# OSSI-1_Interface_Board.net
KiCad netlist of a schematic drawn in EAGLE
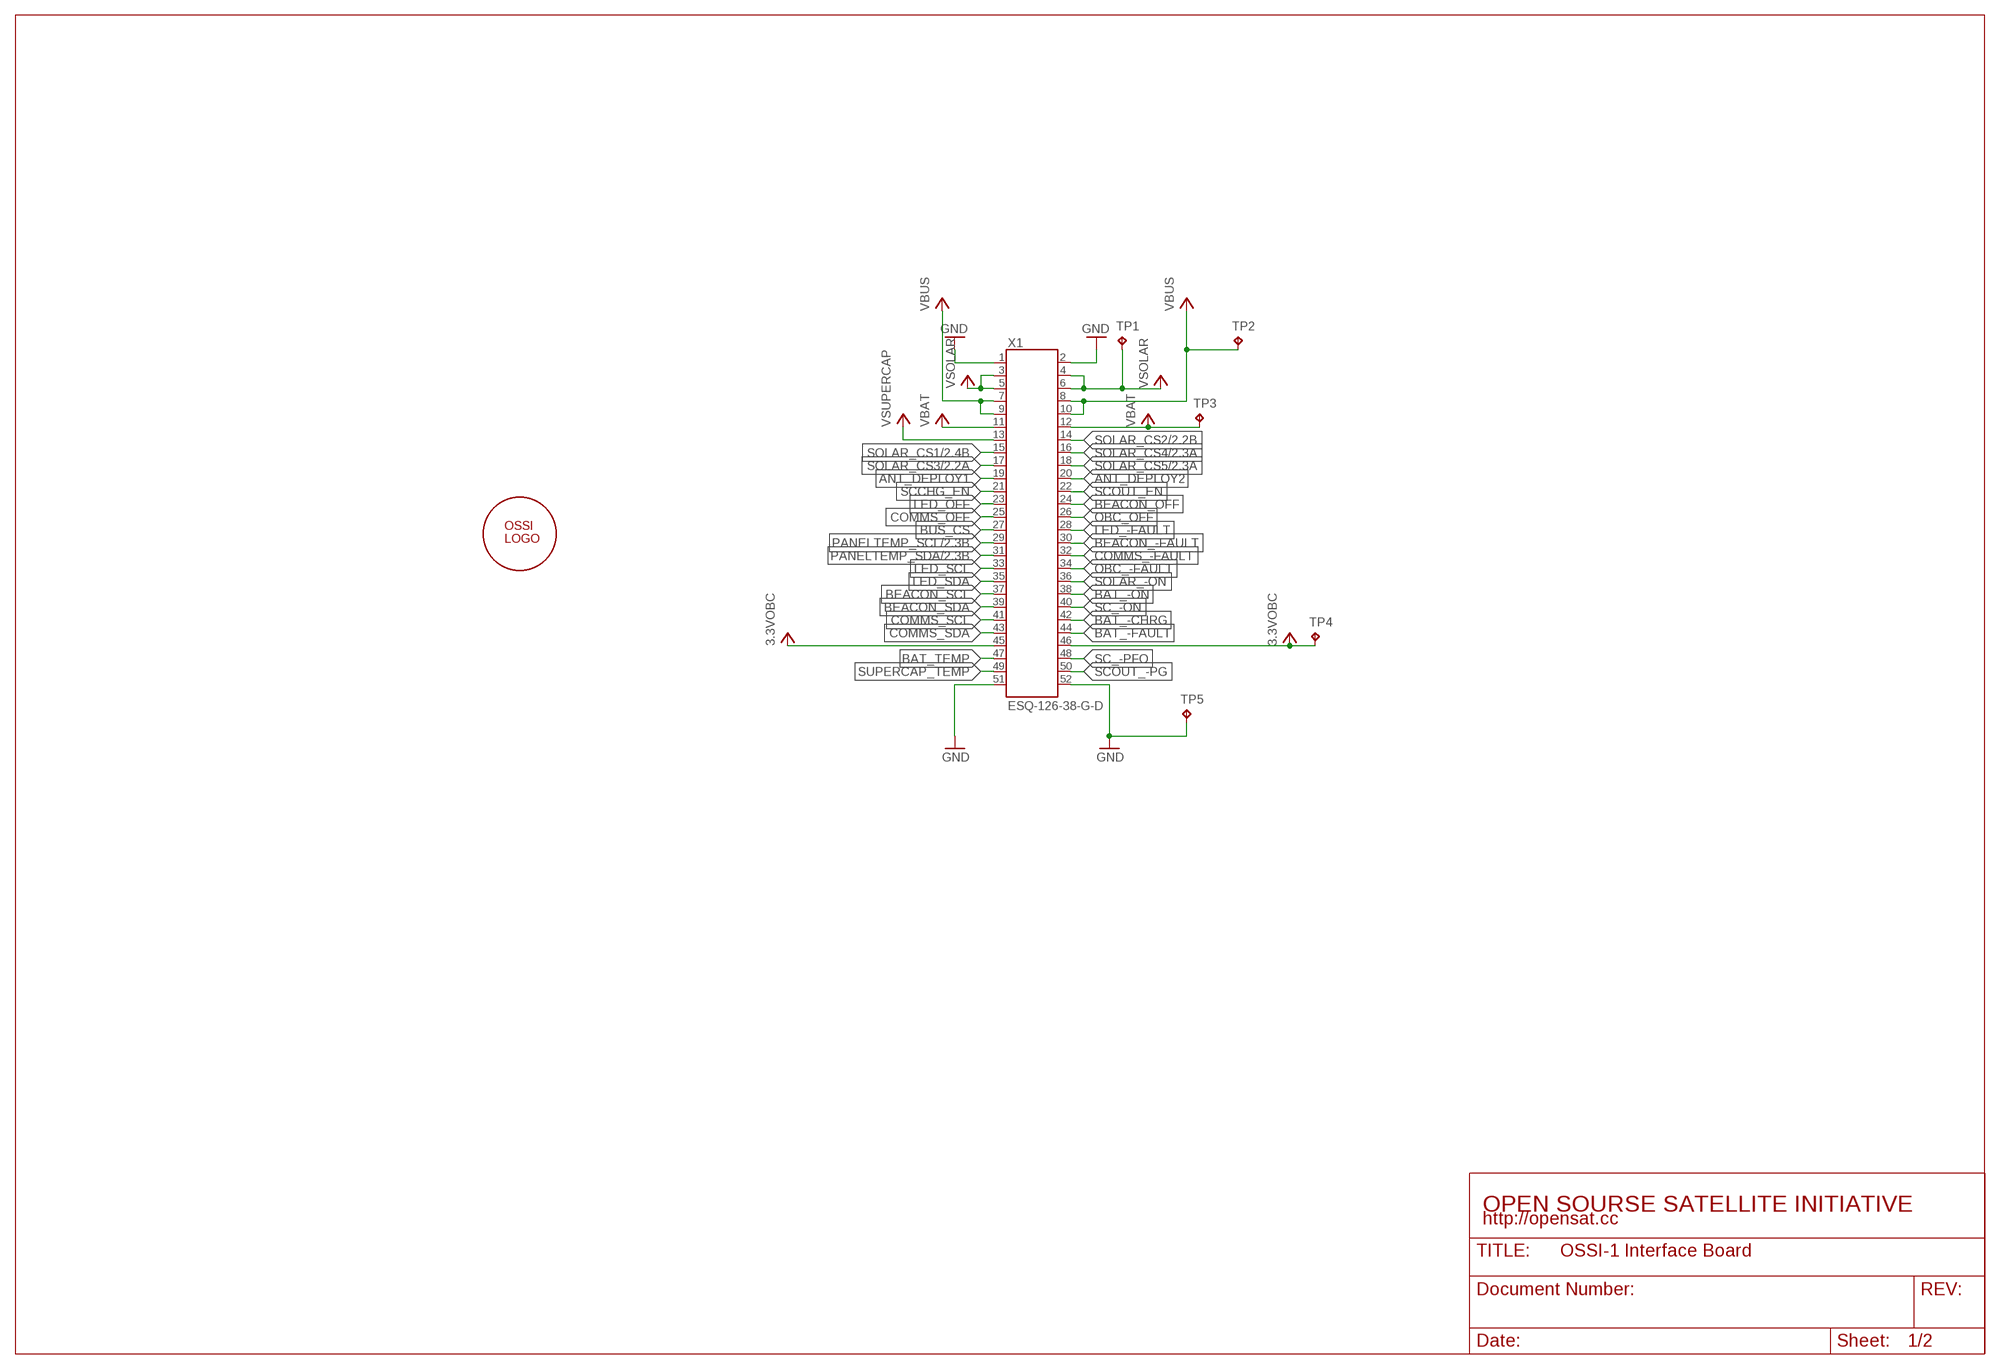
[diagram p0: schematic, sheet 1]
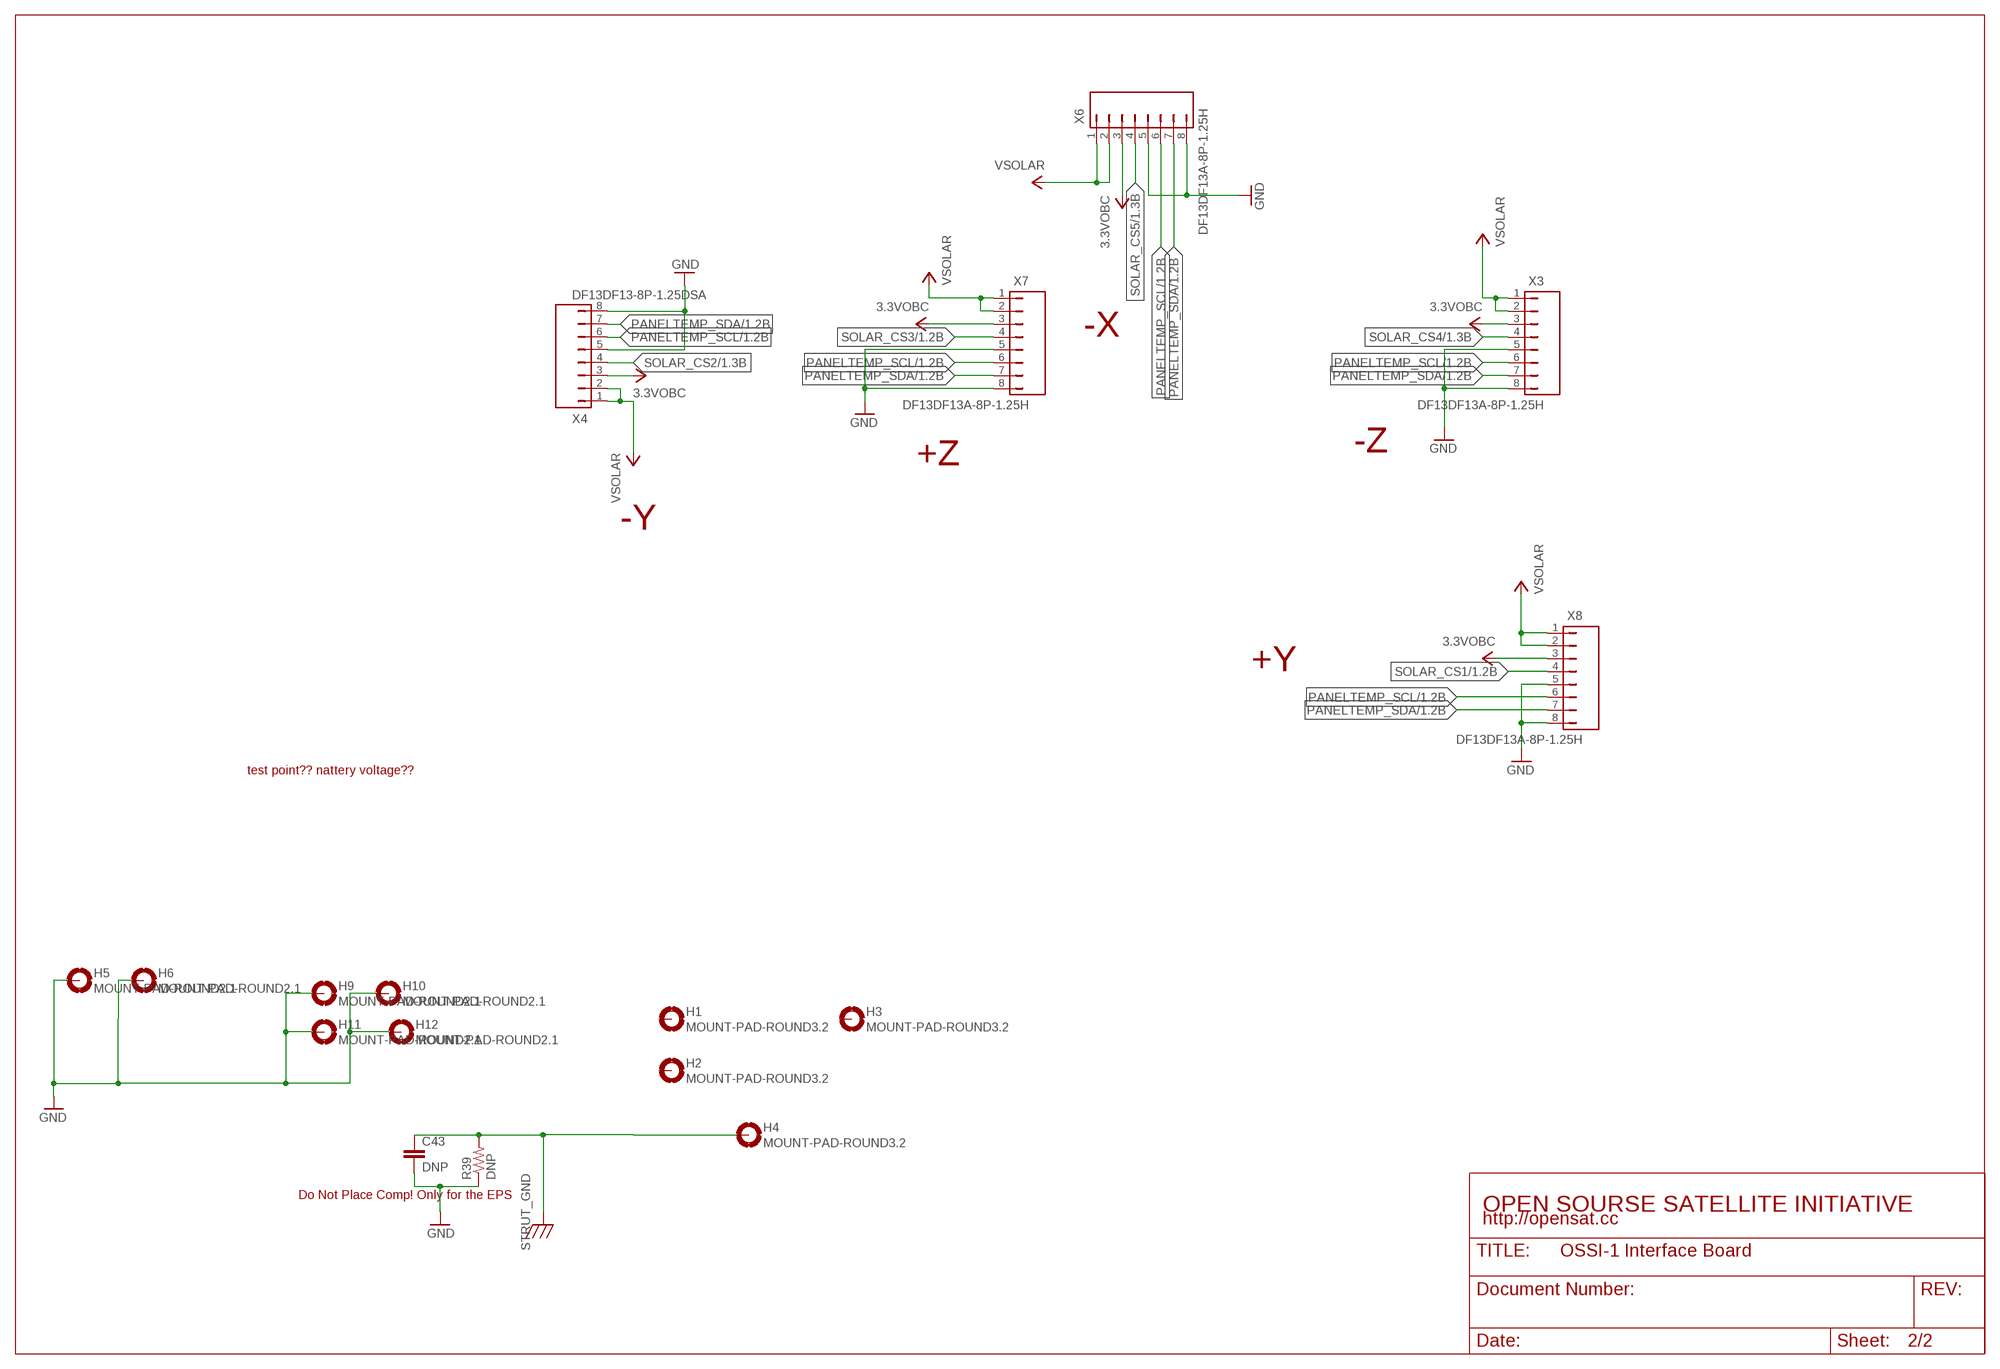
[diagram p1: schematic, sheet 2]

(export (version "E")
  (design (tool "Eeschema 10.0.6"))
  (components
    (comp (ref "TP1")
      (value "TP")
      (footprint "eagle-import:TP-13")
      (libsource (lib "eagle-import") (part "TP"))
    )
    (comp (ref "TP2")
      (value "TP")
      (footprint "eagle-import:TP-13")
      (libsource (lib "eagle-import") (part "TP"))
    )
    (comp (ref "TP3")
      (value "TP")
      (footprint "eagle-import:TP-13")
      (libsource (lib "eagle-import") (part "TP"))
    )
    (comp (ref "TP4")
      (value "TP")
      (footprint "eagle-import:TP-13")
      (libsource (lib "eagle-import") (part "TP"))
    )
    (comp (ref "TP5")
      (value "TP")
      (footprint "eagle-import:TP-13")
      (libsource (lib "eagle-import") (part "TP"))
    )
    (comp (ref "U$1")
      (value "OSSILOGO-10")
      (footprint "eagle-import:OSSILOGO1010")
      (libsource (lib "eagle-import") (part "OSSILOGO-10"))
    )
    (comp (ref "X1")
      (value "ESQ-126-38-G-D")
      (footprint "eagle-import:ESQ-126-XX-X-D")
      (libsource (lib "eagle-import") (part "ESQ-126-38-G-D"))
    )
    (comp (ref "C43")
      (value "DNP")
      (footprint "eagle-import:C0805(2012)")
      (libsource (lib "eagle-import") (part "C0805(2012)"))
    )
    (comp (ref "H1")
      (value "MOUNT-PAD-ROUND3.2")
      (footprint "eagle-import:3.2-PAD-ROUND")
      (libsource (lib "eagle-import") (part "MOUNT-PAD-ROUND3.2"))
    )
    (comp (ref "H2")
      (value "MOUNT-PAD-ROUND3.2")
      (footprint "eagle-import:3.2-PAD-ROUND")
      (libsource (lib "eagle-import") (part "MOUNT-PAD-ROUND3.2"))
    )
    (comp (ref "H3")
      (value "MOUNT-PAD-ROUND3.2")
      (footprint "eagle-import:3.2-PAD-ROUND")
      (libsource (lib "eagle-import") (part "MOUNT-PAD-ROUND3.2"))
    )
    (comp (ref "H4")
      (value "MOUNT-PAD-ROUND3.2")
      (footprint "eagle-import:3.2-PAD-ROUND")
      (libsource (lib "eagle-import") (part "MOUNT-PAD-ROUND3.2"))
    )
    (comp (ref "H5")
      (value "MOUNT-PAD-ROUND2.1")
      (footprint "eagle-import:2.1-PAD-ROUND")
      (libsource (lib "eagle-import") (part "MOUNT-PAD-ROUND2.1"))
    )
    (comp (ref "H6")
      (value "MOUNT-PAD-ROUND2.1")
      (footprint "eagle-import:2.1-PAD-ROUND")
      (libsource (lib "eagle-import") (part "MOUNT-PAD-ROUND2.1"))
    )
    (comp (ref "H9")
      (value "MOUNT-PAD-ROUND2.1")
      (footprint "eagle-import:2.1-PAD-ROUND")
      (libsource (lib "eagle-import") (part "MOUNT-PAD-ROUND2.1"))
    )
    (comp (ref "H10")
      (value "MOUNT-PAD-ROUND2.1")
      (footprint "eagle-import:2.1-PAD-ROUND")
      (libsource (lib "eagle-import") (part "MOUNT-PAD-ROUND2.1"))
    )
    (comp (ref "H11")
      (value "MOUNT-PAD-ROUND2.1")
      (footprint "eagle-import:2.1-PAD-ROUND")
      (libsource (lib "eagle-import") (part "MOUNT-PAD-ROUND2.1"))
    )
    (comp (ref "H12")
      (value "MOUNT-PAD-ROUND2.1")
      (footprint "eagle-import:2.1-PAD-ROUND")
      (libsource (lib "eagle-import") (part "MOUNT-PAD-ROUND2.1"))
    )
    (comp (ref "R39")
      (value "DNP")
      (footprint "eagle-import:WSL1206")
      (libsource (lib "eagle-import") (part "RWSL1206"))
    )
    (comp (ref "X3")
      (value "DF13DF13A-8P-1.25H")
      (footprint "eagle-import:DF13A-8P")
      (libsource (lib "eagle-import") (part "DF13DF13A-8P-1.25H"))
    )
    (comp (ref "X4")
      (value "DF13DF13-8P-1.25DSA")
      (footprint "eagle-import:DF13-8P-1.25DSA")
      (libsource (lib "eagle-import") (part "DF13DF13-8P-1.25DSA"))
    )
    (comp (ref "X6")
      (value "DF13DF13A-8P-1.25H")
      (footprint "eagle-import:DF13A-8P")
      (libsource (lib "eagle-import") (part "DF13DF13A-8P-1.25H"))
    )
    (comp (ref "X7")
      (value "DF13DF13A-8P-1.25H")
      (footprint "eagle-import:DF13A-8P")
      (libsource (lib "eagle-import") (part "DF13DF13A-8P-1.25H"))
    )
    (comp (ref "X8")
      (value "DF13DF13A-8P-1.25H")
      (footprint "eagle-import:DF13A-8P")
      (libsource (lib "eagle-import") (part "DF13DF13A-8P-1.25H"))
    )
  )
  (nets
    (net (code "1") (name "3.3VOBC") (class "Default")
      (node (ref "TP4") (pin "TP") (pinfunction "TP_TP") (pintype "input"))
      (node (ref "X1") (pin "45") (pinfunction "45_45") (pintype "bidirectional"))
      (node (ref "X1") (pin "46") (pinfunction "46_46") (pintype "bidirectional"))
      (node (ref "X3") (pin "3") (pinfunction "3_3") (pintype "passive"))
      (node (ref "X4") (pin "3") (pinfunction "3_3") (pintype "passive"))
      (node (ref "X6") (pin "3") (pinfunction "3_3") (pintype "passive"))
      (node (ref "X7") (pin "3") (pinfunction "3_3") (pintype "passive"))
      (node (ref "X8") (pin "3") (pinfunction "3_3") (pintype "passive"))
    )
    (net (code "2") (name "ANT_DEPLOY1") (class "Default")
      (node (ref "X1") (pin "19") (pinfunction "19_19") (pintype "bidirectional"))
    )
    (net (code "3") (name "ANT_DEPLOY2") (class "Default")
      (node (ref "X1") (pin "20") (pinfunction "20_20") (pintype "bidirectional"))
    )
    (net (code "4") (name "BAT_-CHRG") (class "Default")
      (node (ref "X1") (pin "42") (pinfunction "42_42") (pintype "bidirectional"))
    )
    (net (code "5") (name "BAT_-FAULT") (class "Default")
      (node (ref "X1") (pin "44") (pinfunction "44_44") (pintype "bidirectional"))
    )
    (net (code "6") (name "BAT_-ON") (class "Default")
      (node (ref "X1") (pin "38") (pinfunction "38_38") (pintype "bidirectional"))
    )
    (net (code "7") (name "BAT_TEMP") (class "Default")
      (node (ref "X1") (pin "47") (pinfunction "47_47") (pintype "bidirectional"))
    )
    (net (code "8") (name "BEACON_-FAULT") (class "Default")
      (node (ref "X1") (pin "30") (pinfunction "30_30") (pintype "bidirectional"))
    )
    (net (code "9") (name "BEACON_OFF") (class "Default")
      (node (ref "X1") (pin "24") (pinfunction "24_24") (pintype "bidirectional"))
    )
    (net (code "10") (name "BEACON_SCL") (class "Default")
      (node (ref "X1") (pin "37") (pinfunction "37_37") (pintype "bidirectional"))
    )
    (net (code "11") (name "BEACON_SDA") (class "Default")
      (node (ref "X1") (pin "39") (pinfunction "39_39") (pintype "bidirectional"))
    )
    (net (code "12") (name "BUS_CS") (class "Default")
      (node (ref "X1") (pin "27") (pinfunction "27_27") (pintype "bidirectional"))
    )
    (net (code "13") (name "COMMS_-FAULT") (class "Default")
      (node (ref "X1") (pin "32") (pinfunction "32_32") (pintype "bidirectional"))
    )
    (net (code "14") (name "COMMS_OFF") (class "Default")
      (node (ref "X1") (pin "25") (pinfunction "25_25") (pintype "bidirectional"))
    )
    (net (code "15") (name "COMMS_SCL") (class "Default")
      (node (ref "X1") (pin "41") (pinfunction "41_41") (pintype "bidirectional"))
    )
    (net (code "16") (name "COMMS_SDA") (class "Default")
      (node (ref "X1") (pin "43") (pinfunction "43_43") (pintype "bidirectional"))
    )
    (net (code "17") (name "GND") (class "Default")
      (node (ref "C43") (pin "2") (pinfunction "2_2") (pintype "passive"))
      (node (ref "H10") (pin "B3,2") (pinfunction "MOUNT_B3,2") (pintype "passive"))
      (node (ref "H11") (pin "B3,2") (pinfunction "MOUNT_B3,2") (pintype "passive"))
      (node (ref "H12") (pin "B3,2") (pinfunction "MOUNT_B3,2") (pintype "passive"))
      (node (ref "H5") (pin "B3,2") (pinfunction "MOUNT_B3,2") (pintype "passive"))
      (node (ref "H6") (pin "B3,2") (pinfunction "MOUNT_B3,2") (pintype "passive"))
      (node (ref "H9") (pin "B3,2") (pinfunction "MOUNT_B3,2") (pintype "passive"))
      (node (ref "R39") (pin "P$1") (pinfunction "1_P$1") (pintype "passive"))
      (node (ref "TP5") (pin "TP") (pinfunction "TP_TP") (pintype "input"))
      (node (ref "X1") (pin "1") (pinfunction "1_1") (pintype "bidirectional"))
      (node (ref "X1") (pin "2") (pinfunction "2_2") (pintype "bidirectional"))
      (node (ref "X1") (pin "51") (pinfunction "51_51") (pintype "bidirectional"))
      (node (ref "X1") (pin "52") (pinfunction "52_52") (pintype "bidirectional"))
      (node (ref "X3") (pin "5") (pinfunction "5_5") (pintype "passive"))
      (node (ref "X3") (pin "8") (pinfunction "8_8") (pintype "passive"))
      (node (ref "X4") (pin "5") (pinfunction "5_5") (pintype "passive"))
      (node (ref "X4") (pin "8") (pinfunction "8_8") (pintype "passive"))
      (node (ref "X6") (pin "5") (pinfunction "5_5") (pintype "passive"))
      (node (ref "X6") (pin "8") (pinfunction "8_8") (pintype "passive"))
      (node (ref "X7") (pin "5") (pinfunction "5_5") (pintype "passive"))
      (node (ref "X7") (pin "8") (pinfunction "8_8") (pintype "passive"))
      (node (ref "X8") (pin "5") (pinfunction "5_5") (pintype "passive"))
      (node (ref "X8") (pin "8") (pinfunction "8_8") (pintype "passive"))
    )
    (net (code "18") (name "LED_-FAULT") (class "Default")
      (node (ref "X1") (pin "28") (pinfunction "28_28") (pintype "bidirectional"))
    )
    (net (code "19") (name "LED_OFF") (class "Default")
      (node (ref "X1") (pin "23") (pinfunction "23_23") (pintype "bidirectional"))
    )
    (net (code "20") (name "LED_SCL") (class "Default")
      (node (ref "X1") (pin "33") (pinfunction "33_33") (pintype "bidirectional"))
    )
    (net (code "21") (name "LED_SDA") (class "Default")
      (node (ref "X1") (pin "35") (pinfunction "35_35") (pintype "bidirectional"))
    )
    (net (code "22") (name "OBC_-FAULT") (class "Default")
      (node (ref "X1") (pin "34") (pinfunction "34_34") (pintype "bidirectional"))
    )
    (net (code "23") (name "OBC_OFF") (class "Default")
      (node (ref "X1") (pin "26") (pinfunction "26_26") (pintype "bidirectional"))
    )
    (net (code "24") (name "PANELTEMP_SCL") (class "Default")
      (node (ref "X1") (pin "29") (pinfunction "29_29") (pintype "bidirectional"))
      (node (ref "X3") (pin "6") (pinfunction "6_6") (pintype "passive"))
      (node (ref "X4") (pin "6") (pinfunction "6_6") (pintype "passive"))
      (node (ref "X6") (pin "6") (pinfunction "6_6") (pintype "passive"))
      (node (ref "X7") (pin "6") (pinfunction "6_6") (pintype "passive"))
      (node (ref "X8") (pin "6") (pinfunction "6_6") (pintype "passive"))
    )
    (net (code "25") (name "PANELTEMP_SDA") (class "Default")
      (node (ref "X1") (pin "31") (pinfunction "31_31") (pintype "bidirectional"))
      (node (ref "X3") (pin "7") (pinfunction "7_7") (pintype "passive"))
      (node (ref "X4") (pin "7") (pinfunction "7_7") (pintype "passive"))
      (node (ref "X6") (pin "7") (pinfunction "7_7") (pintype "passive"))
      (node (ref "X7") (pin "7") (pinfunction "7_7") (pintype "passive"))
      (node (ref "X8") (pin "7") (pinfunction "7_7") (pintype "passive"))
    )
    (net (code "26") (name "SCCHG_EN") (class "Default")
      (node (ref "X1") (pin "21") (pinfunction "21_21") (pintype "bidirectional"))
    )
    (net (code "27") (name "SCOUT_-PG") (class "Default")
      (node (ref "X1") (pin "50") (pinfunction "50_50") (pintype "bidirectional"))
    )
    (net (code "28") (name "SCOUT_EN") (class "Default")
      (node (ref "X1") (pin "22") (pinfunction "22_22") (pintype "bidirectional"))
    )
    (net (code "29") (name "SC_-ON") (class "Default")
      (node (ref "X1") (pin "40") (pinfunction "40_40") (pintype "bidirectional"))
    )
    (net (code "30") (name "SC_-PFO") (class "Default")
      (node (ref "X1") (pin "48") (pinfunction "48_48") (pintype "bidirectional"))
    )
    (net (code "31") (name "SOLAR_-ON") (class "Default")
      (node (ref "X1") (pin "36") (pinfunction "36_36") (pintype "bidirectional"))
    )
    (net (code "32") (name "SOLAR_CS1") (class "Default")
      (node (ref "X1") (pin "15") (pinfunction "15_15") (pintype "bidirectional"))
      (node (ref "X8") (pin "4") (pinfunction "4_4") (pintype "passive"))
    )
    (net (code "33") (name "SOLAR_CS2") (class "Default")
      (node (ref "X1") (pin "14") (pinfunction "14_14") (pintype "bidirectional"))
      (node (ref "X4") (pin "4") (pinfunction "4_4") (pintype "passive"))
    )
    (net (code "34") (name "SOLAR_CS3") (class "Default")
      (node (ref "X1") (pin "17") (pinfunction "17_17") (pintype "bidirectional"))
      (node (ref "X7") (pin "4") (pinfunction "4_4") (pintype "passive"))
    )
    (net (code "35") (name "SOLAR_CS4") (class "Default")
      (node (ref "X1") (pin "16") (pinfunction "16_16") (pintype "bidirectional"))
      (node (ref "X3") (pin "4") (pinfunction "4_4") (pintype "passive"))
    )
    (net (code "36") (name "SOLAR_CS5") (class "Default")
      (node (ref "X1") (pin "18") (pinfunction "18_18") (pintype "bidirectional"))
      (node (ref "X6") (pin "4") (pinfunction "4_4") (pintype "passive"))
    )
    (net (code "37") (name "STRUT_GND") (class "Default")
      (node (ref "C43") (pin "1") (pinfunction "1_1") (pintype "passive"))
      (node (ref "H4") (pin "B3,2") (pinfunction "MOUNT_B3,2") (pintype "passive"))
      (node (ref "R39") (pin "P$2") (pinfunction "2_P$2") (pintype "passive"))
    )
    (net (code "38") (name "SUPERCAP_TEMP") (class "Default")
      (node (ref "X1") (pin "49") (pinfunction "49_49") (pintype "bidirectional"))
    )
    (net (code "39") (name "VBAT") (class "Default")
      (node (ref "TP3") (pin "TP") (pinfunction "TP_TP") (pintype "input"))
      (node (ref "X1") (pin "11") (pinfunction "11_11") (pintype "bidirectional"))
      (node (ref "X1") (pin "12") (pinfunction "12_12") (pintype "bidirectional"))
    )
    (net (code "40") (name "VBUS") (class "Default")
      (node (ref "TP2") (pin "TP") (pinfunction "TP_TP") (pintype "input"))
      (node (ref "X1") (pin "10") (pinfunction "10_10") (pintype "bidirectional"))
      (node (ref "X1") (pin "7") (pinfunction "7_7") (pintype "bidirectional"))
      (node (ref "X1") (pin "8") (pinfunction "8_8") (pintype "bidirectional"))
      (node (ref "X1") (pin "9") (pinfunction "9_9") (pintype "bidirectional"))
    )
    (net (code "41") (name "VSOLAR") (class "Default")
      (node (ref "TP1") (pin "TP") (pinfunction "TP_TP") (pintype "input"))
      (node (ref "X1") (pin "3") (pinfunction "3_3") (pintype "bidirectional"))
      (node (ref "X1") (pin "4") (pinfunction "4_4") (pintype "bidirectional"))
      (node (ref "X1") (pin "5") (pinfunction "5_5") (pintype "bidirectional"))
      (node (ref "X1") (pin "6") (pinfunction "6_6") (pintype "bidirectional"))
      (node (ref "X3") (pin "1") (pinfunction "1_1") (pintype "passive"))
      (node (ref "X3") (pin "2") (pinfunction "2_2") (pintype "passive"))
      (node (ref "X4") (pin "1") (pinfunction "1_1") (pintype "passive"))
      (node (ref "X4") (pin "2") (pinfunction "2_2") (pintype "passive"))
      (node (ref "X6") (pin "1") (pinfunction "1_1") (pintype "passive"))
      (node (ref "X6") (pin "2") (pinfunction "2_2") (pintype "passive"))
      (node (ref "X7") (pin "1") (pinfunction "1_1") (pintype "passive"))
      (node (ref "X7") (pin "2") (pinfunction "2_2") (pintype "passive"))
      (node (ref "X8") (pin "1") (pinfunction "1_1") (pintype "passive"))
      (node (ref "X8") (pin "2") (pinfunction "2_2") (pintype "passive"))
    )
    (net (code "42") (name "VSUPERCAP") (class "Default")
      (node (ref "X1") (pin "13") (pinfunction "13_13") (pintype "bidirectional"))
    )
    (net (code "43") (name "unconnected-(H1-MOUNT-PadB3,2)") (class "Default")
      (node (ref "H1") (pin "B3,2") (pinfunction "MOUNT_B3,2") (pintype "passive"))
    )
    (net (code "44") (name "unconnected-(H2-MOUNT-PadB3,2)") (class "Default")
      (node (ref "H2") (pin "B3,2") (pinfunction "MOUNT_B3,2") (pintype "passive"))
    )
    (net (code "45") (name "unconnected-(H3-MOUNT-PadB3,2)") (class "Default")
      (node (ref "H3") (pin "B3,2") (pinfunction "MOUNT_B3,2") (pintype "passive"))
    )
  )
)
